# MCU_Extras.net
KiCad netlist of a schematic drawn in Altium Designer
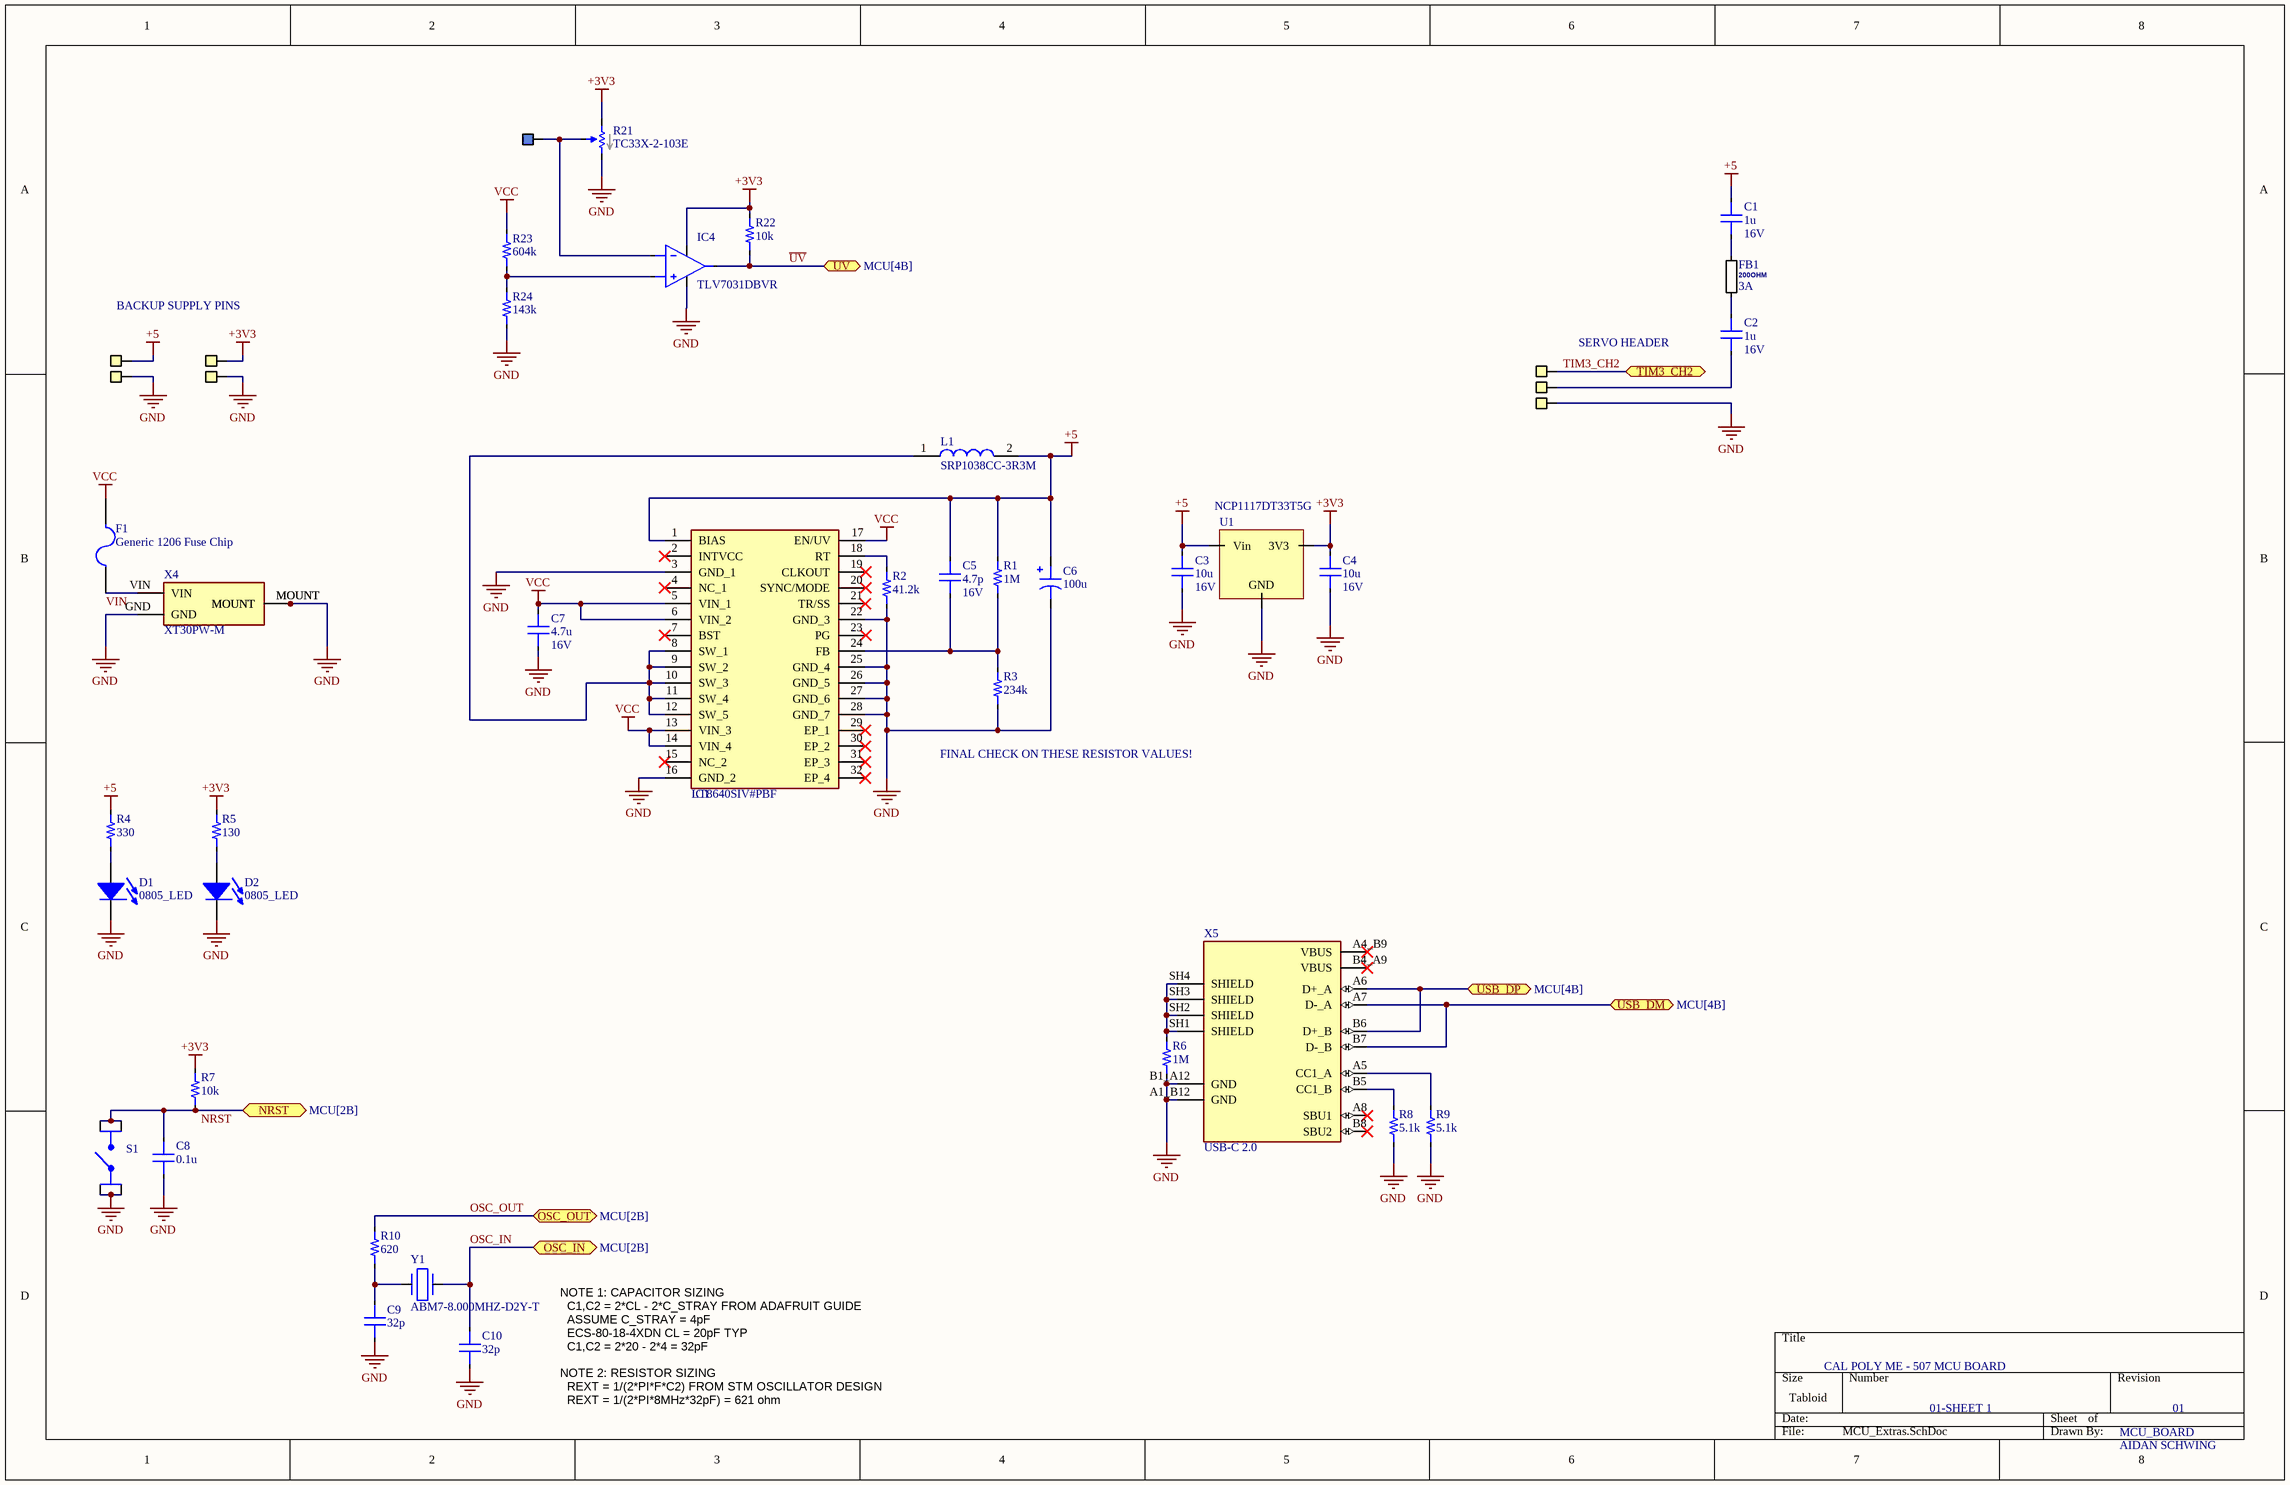
[diagram p0: MCU_Extras.SchDoc]

(export (version "E")
  (design (tool "Eeschema 10.0.6"))
  (components
    (comp (ref "C1")
      (value "1u")
      (footprint "0603_CAP")
      (fields (field (name "VOLTAGE") "16V") (field (name "Comment") "Capacitor"))
      (libsource (lib "Capacitors") (part "Capacitor"))
    )
    (comp (ref "C2")
      (value "1u")
      (footprint "0603_CAP")
      (fields (field (name "VOLTAGE") "16V") (field (name "Comment") "Capacitor"))
      (libsource (lib "Capacitors") (part "Capacitor"))
    )
    (comp (ref "C3")
      (value "10u")
      (footprint "0805_CAP")
      (fields (field (name "VOLTAGE") "16V") (field (name "Comment") "Capacitor"))
      (libsource (lib "Capacitors") (part "Capacitor"))
    )
    (comp (ref "C4")
      (value "10u")
      (footprint "0805_CAP")
      (fields (field (name "VOLTAGE") "16V") (field (name "Comment") "Capacitor"))
      (libsource (lib "Capacitors") (part "Capacitor"))
    )
    (comp (ref "C5")
      (value "4.7p")
      (footprint "0603_CAP")
      (fields (field (name "VOLTAGE") "16V") (field (name "Comment") "Capacitor"))
      (libsource (lib "Capacitors") (part "Capacitor"))
    )
    (comp (ref "C6")
      (value "100u")
      (footprint "6.60x6.60x8.00mm_E_CAP")
      (description "CAP ALUM 100UF 20% 16V SMD")
      (fields (field (name "Comment") "865080343009"))
      (libsource (lib "Capacitors") (part "865080343009"))
    )
    (comp (ref "C7")
      (value "4.7u")
      (footprint "0805_CAP")
      (fields (field (name "VOLTAGE") "16V") (field (name "Comment") "Capacitor"))
      (libsource (lib "Capacitors") (part "Capacitor"))
    )
    (comp (ref "C8")
      (value "0.1u")
      (footprint "0805_CAP")
      (fields (field (name "Comment") "Capacitor"))
      (libsource (lib "Capacitors") (part "Capacitor"))
    )
    (comp (ref "C9")
      (value "32p")
      (footprint "0805_CAP")
      (fields (field (name "Comment") "Capacitor"))
      (libsource (lib "Capacitors") (part "Capacitor"))
    )
    (comp (ref "C10")
      (value "32p")
      (footprint "0805_CAP")
      (fields (field (name "Comment") "Capacitor"))
      (libsource (lib "Capacitors") (part "Capacitor"))
    )
    (comp (ref "D1")
      (value "0805_LED")
      (footprint "0805_LED")
      (description "Generic 0805 LED")
      (libsource (lib "Diodes") (part "0805_LED"))
    )
    (comp (ref "D2")
      (value "0805_LED")
      (footprint "0805_LED")
      (description "Generic 0805 LED")
      (libsource (lib "Diodes") (part "0805_LED"))
    )
    (comp (ref "F1")
      (value "Generic 1206 Fuse Chip")
      (footprint "1206_RES")
      (libsource (lib "Fuses") (part "Generic 1206 Fuse Chip"))
    )
    (comp (ref "FB1")
      (value "*")
      (footprint "0805_Ferrite")
      (fields (field (name "=Z@100MHZ") "200OHM") (field (name "IMAX") "3A"))
      (libsource (lib "Magnetic") (part "ChipFerrite"))
    )
    (comp (ref "IC1")
      (value "LT8640SIV#PBF")
      (footprint "507_Part_Footprints:LT8640SIVPBF")
      (description "Integrated Circuit")
      (fields (field (name "MOUSER PART NUMBER") "584-LT8640SIVPBF"))
      (libsource (lib "507_Parts") (part "LT8640SIV#PBF"))
    )
    (comp (ref "IC4")
      (value "TLV7031DBVR")
      (footprint "507_Part_Footprints:SOT95P280X145-5N")
      (fields (field (name "MOUSER PART NUMBER") "595-TLV7031DBVR"))
      (libsource (lib "507_Parts") (part "TLV7031DBVR"))
    )
    (comp (ref "L1")
      (value "SRP1038CC-3R3M")
      (footprint "INDPM110100X400N")
      (description "Inductor, 3.3uH")
      (fields (field (name "MANUFACTURER_PART_NUMBER") "SRP1038CC-4R7M"))
      (libsource (lib "507_Parts") (part "SRP1038CC-3R3M"))
    )
    (comp (ref "R1")
      (value "1M")
      (footprint "0805_RES")
      (fields (field (name "Comment") "Resistor"))
      (libsource (lib "Resistors") (part "Resistor"))
    )
    (comp (ref "R2")
      (value "41.2k")
      (footprint "0805_RES")
      (fields (field (name "Comment") "Resistor"))
      (libsource (lib "Resistors") (part "Resistor"))
    )
    (comp (ref "R3")
      (value "234k")
      (footprint "0805_RES")
      (fields (field (name "Comment") "Resistor"))
      (libsource (lib "Resistors") (part "Resistor"))
    )
    (comp (ref "R4")
      (value "330")
      (footprint "0603_RES")
      (fields (field (name "Comment") "Resistor"))
      (libsource (lib "Resistors") (part "Resistor"))
    )
    (comp (ref "R5")
      (value "130")
      (footprint "0603_RES")
      (fields (field (name "Comment") "Resistor"))
      (libsource (lib "Resistors") (part "Resistor"))
    )
    (comp (ref "R6")
      (value "1M")
      (footprint "0805_RES")
      (fields (field (name "Comment") "Resistor"))
      (libsource (lib "Resistors") (part "Resistor"))
    )
    (comp (ref "R7")
      (value "10k")
      (footprint "0603_RES")
      (fields (field (name "Comment") "Resistor"))
      (libsource (lib "Resistors") (part "Resistor"))
    )
    (comp (ref "R8")
      (value "5.1k")
      (footprint "0805_RES")
      (fields (field (name "Comment") "Resistor"))
      (libsource (lib "Resistors") (part "Resistor"))
    )
    (comp (ref "R9")
      (value "5.1k")
      (footprint "0805_RES")
      (fields (field (name "Comment") "Resistor"))
      (libsource (lib "Resistors") (part "Resistor"))
    )
    (comp (ref "R10")
      (value "620")
      (footprint "0805_RES")
      (fields (field (name "Comment") "Resistor"))
      (libsource (lib "Resistors") (part "Resistor"))
    )
    (comp (ref "R21")
      (value "TC33X-2-103E")
      (footprint "35WR")
      (description "0.1W, 1/10W J Lead Surface Mount Trimmer Potentiometer Cermet Turn Top Adjustment")
      (fields (field (name "POWER") "1/10W"))
      (libsource (lib "Resistors") (part "TC33X-2-103E"))
    )
    (comp (ref "R22")
      (value "10k")
      (footprint "0805_RES")
      (fields (field (name "Comment") "Resistor"))
      (libsource (lib "Resistors") (part "Resistor"))
    )
    (comp (ref "R23")
      (value "604k")
      (footprint "0805_RES")
      (fields (field (name "Comment") "Resistor"))
      (libsource (lib "Resistors") (part "Resistor"))
    )
    (comp (ref "R24")
      (value "143k")
      (footprint "0805_RES")
      (fields (field (name "Comment") "Resistor"))
      (libsource (lib "Resistors") (part "Resistor"))
    )
    (comp (ref "S1")
      (value "TactileSwitch")
      (footprint "6mmTactileSwitch_ThroughHole")
      (description "Generic 6mm Through Hole Tactile Switch")
      (libsource (lib "ElectroMechanical") (part "TactileSwitch"))
    )
    (comp (ref "U1")
      (value "NCP1117DT33T5G")
      (footprint "DPAK3_TO-252-3")
      (description "IC REG LINEAR 3.3V 1A DPAK")
      (libsource (lib "Power") (part "NCP1117DT33T5G"))
    )
    (comp (ref "X1")
      (value "GenericPinHeader(0.1in)")
      (footprint "GenericPinHeader(.1in)")
      (description "Generic .1in(2.54mm) pitch pin header")
      (libsource (lib "Connectors") (part "GenericPinHeader(0.1in)"))
    )
    (comp (ref "X2")
      (value "GenericPinHeader(0.1in)")
      (footprint "GenericPinHeader(.1in)")
      (description "Generic .1in(2.54mm) pitch pin header")
      (libsource (lib "Connectors") (part "GenericPinHeader(0.1in)"))
    )
    (comp (ref "X3")
      (value "GenericPinHeader(0.1in)")
      (footprint "GenericPinHeader(.1in)")
      (description "Generic .1in(2.54mm) pitch pin header")
      (libsource (lib "Connectors") (part "GenericPinHeader(0.1in)"))
    )
    (comp (ref "X4")
      (value "XT30PW-M")
      (footprint "XT30PWM")
      (description "Socket; DC supply; XT30; male; PIN: 2; on PCBs; THT; yellow; 15A; 500V")
      (libsource (lib "Connectors") (part "XT30PW-M"))
    )
    (comp (ref "X5")
      (value "USB-C 2.0")
      (footprint "AMPHENOL_12402012E212A")
      (description "CONN RCP USB2.0 TYP C 24P SMD RA")
      (fields (field (name "MF") "{'manufacturer': u'Amphenol'}") (field (name "MP") "12402012E212A"))
      (libsource (lib "507_Parts") (part "12402012E212A"))
    )
    (comp (ref "X11")
      (value "HeaderPad")
      (footprint "HeaderPad")
      (description "Pad for pin header")
      (libsource (lib "Connectors") (part "HeaderPad"))
    )
    (comp (ref "X19")
      (value "GenericPinHeader(0.1in)")
      (footprint "GenericPinHeader(.1in)")
      (description "Generic .1in(2.54mm) pitch pin header")
      (libsource (lib "Connectors") (part "GenericPinHeader(0.1in)"))
    )
    (comp (ref "X22")
      (value "GenericPinHeader(0.1in)")
      (footprint "GenericPinHeader(.1in)")
      (description "Generic .1in(2.54mm) pitch pin header")
      (libsource (lib "Connectors") (part "GenericPinHeader(0.1in)"))
    )
    (comp (ref "X23")
      (value "GenericPinHeader(0.1in)")
      (footprint "GenericPinHeader(.1in)")
      (description "Generic .1in(2.54mm) pitch pin header")
      (libsource (lib "Connectors") (part "GenericPinHeader(0.1in)"))
    )
    (comp (ref "X26")
      (value "GenericPinHeader(0.1in)")
      (footprint "GenericPinHeader(.1in)")
      (description "Generic .1in(2.54mm) pitch pin header")
      (libsource (lib "Connectors") (part "GenericPinHeader(0.1in)"))
    )
    (comp (ref "Y1")
      (value "ABM7-8.000MHZ-D2Y-T")
      (footprint "ABM7")
      (description "Crystal or Oscillator")
      (fields (field (name "MOUSER PART NUMBER") "815-ABM7-8-D2Y-T"))
      (libsource (lib "507_Parts") (part "ABM7-8.000MHZ-D2Y-T"))
    )
  )
  (nets
    (net (code "1") (name "+3V3") (class "Default")
      (node (ref "C4") (pin "1") (pinfunction "1_1") (pintype "passive"))
      (node (ref "IC4") (pin "5") (pinfunction "VCC_5") (pintype "passive"))
      (node (ref "R21") (pin "1") (pinfunction "1_1") (pintype "passive"))
      (node (ref "R22") (pin "2") (pinfunction "2_2") (pintype "passive"))
      (node (ref "R5") (pin "2") (pinfunction "2_2") (pintype "passive"))
      (node (ref "R7") (pin "2") (pinfunction "2_2") (pintype "passive"))
      (node (ref "U1") (pin "4") (pinfunction "3V3_4") (pintype "passive"))
      (node (ref "X22") (pin "1") (pinfunction "Pin_1") (pintype "passive"))
    )
    (net (code "2") (name "+5") (class "Default")
      (node (ref "C1") (pin "1") (pinfunction "1_1") (pintype "passive"))
      (node (ref "C3") (pin "1") (pinfunction "1_1") (pintype "passive"))
      (node (ref "C5") (pin "1") (pinfunction "1_1") (pintype "passive"))
      (node (ref "C6") (pin "1") (pinfunction "1_1") (pintype "passive"))
      (node (ref "IC1") (pin "1") (pinfunction "BIAS_1") (pintype "passive"))
      (node (ref "L1") (pin "2") (pinfunction "2_2") (pintype "passive"))
      (node (ref "R1") (pin "2") (pinfunction "2_2") (pintype "passive"))
      (node (ref "R4") (pin "2") (pinfunction "2_2") (pintype "passive"))
      (node (ref "U1") (pin "3") (pinfunction "Vin_3") (pintype "passive"))
      (node (ref "X19") (pin "1") (pinfunction "Pin_1") (pintype "passive"))
    )
    (net (code "3") (name "/NRST") (class "Default")
      (node (ref "C8") (pin "2") (pinfunction "2_2") (pintype "passive"))
      (node (ref "R7") (pin "1") (pinfunction "1_1") (pintype "passive"))
      (node (ref "S1") (pin "3") (pinfunction "3_3") (pintype "passive"))
      (node (ref "S1") (pin "4") (pinfunction "4_4") (pintype "passive"))
    )
    (net (code "4") (name "/OSC_IN") (class "Default")
      (node (ref "C10") (pin "2") (pinfunction "2_2") (pintype "passive"))
      (node (ref "Y1") (pin "2") (pinfunction "2_2") (pintype "passive"))
    )
    (net (code "5") (name "/OSC_OUT") (class "Default")
      (node (ref "R10") (pin "2") (pinfunction "2_2") (pintype "passive"))
    )
    (net (code "6") (name "/TIM3_CH2") (class "Default")
      (node (ref "X1") (pin "1") (pinfunction "Pin_1") (pintype "passive"))
    )
    (net (code "7") (name "/USB_DM") (class "Default")
      (node (ref "X5") (pin "A7") (pinfunction "D-_A_A7") (pintype "bidirectional"))
      (node (ref "X5") (pin "B7") (pinfunction "D-_B_B7") (pintype "bidirectional"))
    )
    (net (code "8") (name "/USB_DP") (class "Default")
      (node (ref "X5") (pin "A6") (pinfunction "D+_A_A6") (pintype "bidirectional"))
      (node (ref "X5") (pin "B6") (pinfunction "D+_B_B6") (pintype "bidirectional"))
    )
    (net (code "9") (name "/VIN") (class "Default")
      (node (ref "F1") (pin "1") (pinfunction "1_1") (pintype "passive"))
      (node (ref "X4") (pin "VIN") (pinfunction "VIN_VIN") (pintype "passive"))
    )
    (net (code "10") (name "/~{UV}") (class "Default")
      (node (ref "IC4") (pin "1") (pinfunction "OUT_1") (pintype "passive"))
      (node (ref "R22") (pin "1") (pinfunction "1_1") (pintype "passive"))
    )
    (net (code "11") (name "GND") (class "Default")
      (node (ref "C10") (pin "1") (pinfunction "1_1") (pintype "passive"))
      (node (ref "C3") (pin "2") (pinfunction "2_2") (pintype "passive"))
      (node (ref "C4") (pin "2") (pinfunction "2_2") (pintype "passive"))
      (node (ref "C6") (pin "2") (pinfunction "2_2") (pintype "passive"))
      (node (ref "C7") (pin "2") (pinfunction "2_2") (pintype "passive"))
      (node (ref "C8") (pin "1") (pinfunction "1_1") (pintype "passive"))
      (node (ref "C9") (pin "1") (pinfunction "1_1") (pintype "passive"))
      (node (ref "D1") (pin "2") (pinfunction "K_2") (pintype "passive"))
      (node (ref "D2") (pin "2") (pinfunction "K_2") (pintype "passive"))
      (node (ref "IC1") (pin "16") (pinfunction "GND_2_16") (pintype "passive"))
      (node (ref "IC1") (pin "22") (pinfunction "GND_3_22") (pintype "passive"))
      (node (ref "IC1") (pin "25") (pinfunction "GND_4_25") (pintype "passive"))
      (node (ref "IC1") (pin "26") (pinfunction "GND_5_26") (pintype "passive"))
      (node (ref "IC1") (pin "27") (pinfunction "GND_6_27") (pintype "passive"))
      (node (ref "IC1") (pin "28") (pinfunction "GND_7_28") (pintype "passive"))
      (node (ref "IC1") (pin "3") (pinfunction "GND_1_3") (pintype "passive"))
      (node (ref "IC4") (pin "2") (pinfunction "VEE_2") (pintype "passive"))
      (node (ref "R2") (pin "1") (pinfunction "1_1") (pintype "passive"))
      (node (ref "R21") (pin "3") (pinfunction "3_3") (pintype "passive"))
      (node (ref "R24") (pin "1") (pinfunction "1_1") (pintype "passive"))
      (node (ref "R3") (pin "1") (pinfunction "1_1") (pintype "passive"))
      (node (ref "R6") (pin "1") (pinfunction "1_1") (pintype "passive"))
      (node (ref "R8") (pin "1") (pinfunction "1_1") (pintype "passive"))
      (node (ref "R9") (pin "1") (pinfunction "1_1") (pintype "passive"))
      (node (ref "S1") (pin "1") (pinfunction "1_1") (pintype "passive"))
      (node (ref "S1") (pin "2") (pinfunction "2_2") (pintype "passive"))
      (node (ref "U1") (pin "1") (pinfunction "GND_1") (pintype "passive"))
      (node (ref "X23") (pin "1") (pinfunction "Pin_1") (pintype "passive"))
      (node (ref "X26") (pin "1") (pinfunction "Pin_1") (pintype "passive"))
      (node (ref "X3") (pin "1") (pinfunction "Pin_1") (pintype "passive"))
      (node (ref "X4") (pin "GND") (pinfunction "GND_GND") (pintype "passive"))
      (node (ref "X4") (pin "MOUNT") (pinfunction "MOUNT_MOUNT") (pintype "passive"))
      (node (ref "X5") (pin "A1_B12") (pinfunction "GND_A1_B12") (pintype "power_in"))
      (node (ref "X5") (pin "B1_A12") (pinfunction "GND_B1_A12") (pintype "power_in"))
    )
    (net (code "12") (name "Net-(C1-Pad2)") (class "Default")
      (node (ref "C1") (pin "2") (pinfunction "2_2") (pintype "passive"))
      (node (ref "FB1") (pin "2") (pinfunction "2_2") (pintype "passive"))
    )
    (net (code "13") (name "Net-(C2-Pad1)") (class "Default")
      (node (ref "C2") (pin "1") (pinfunction "1_1") (pintype "passive"))
      (node (ref "FB1") (pin "1") (pinfunction "1_1") (pintype "passive"))
    )
    (net (code "14") (name "Net-(C9-Pad2)") (class "Default")
      (node (ref "C9") (pin "2") (pinfunction "2_2") (pintype "passive"))
      (node (ref "R10") (pin "1") (pinfunction "1_1") (pintype "passive"))
      (node (ref "Y1") (pin "1") (pinfunction "1_1") (pintype "passive"))
    )
    (net (code "15") (name "Net-(D1-A)") (class "Default")
      (node (ref "D1") (pin "1") (pinfunction "A_1") (pintype "passive"))
      (node (ref "R4") (pin "1") (pinfunction "1_1") (pintype "passive"))
    )
    (net (code "16") (name "Net-(D2-A)") (class "Default")
      (node (ref "D2") (pin "1") (pinfunction "A_1") (pintype "passive"))
      (node (ref "R5") (pin "1") (pinfunction "1_1") (pintype "passive"))
    )
    (net (code "17") (name "Net-(IC1-FB)") (class "Default")
      (node (ref "C5") (pin "2") (pinfunction "2_2") (pintype "passive"))
      (node (ref "IC1") (pin "24") (pinfunction "FB_24") (pintype "passive"))
      (node (ref "R1") (pin "1") (pinfunction "1_1") (pintype "passive"))
      (node (ref "R3") (pin "2") (pinfunction "2_2") (pintype "passive"))
    )
    (net (code "18") (name "Net-(IC1-RT)") (class "Default")
      (node (ref "IC1") (pin "18") (pinfunction "RT_18") (pintype "passive"))
      (node (ref "R2") (pin "2") (pinfunction "2_2") (pintype "passive"))
    )
    (net (code "19") (name "Net-(IC1-SW_1)") (class "Default")
      (node (ref "IC1") (pin "10") (pinfunction "SW_3_10") (pintype "passive"))
      (node (ref "IC1") (pin "11") (pinfunction "SW_4_11") (pintype "passive"))
      (node (ref "IC1") (pin "12") (pinfunction "SW_5_12") (pintype "passive"))
      (node (ref "IC1") (pin "8") (pinfunction "SW_1_8") (pintype "passive"))
      (node (ref "IC1") (pin "9") (pinfunction "SW_2_9") (pintype "passive"))
      (node (ref "L1") (pin "1") (pinfunction "1_1") (pintype "passive"))
    )
    (net (code "20") (name "Net-(IC4-IN+)") (class "Default")
      (node (ref "IC4") (pin "3") (pinfunction "IN+_3") (pintype "passive"))
      (node (ref "R23") (pin "1") (pinfunction "1_1") (pintype "passive"))
      (node (ref "R24") (pin "2") (pinfunction "2_2") (pintype "passive"))
    )
    (net (code "21") (name "Net-(IC4-IN-)") (class "Default")
      (node (ref "IC4") (pin "4") (pinfunction "IN-_4") (pintype "passive"))
      (node (ref "R21") (pin "2") (pinfunction "2_2") (pintype "passive"))
      (node (ref "X11") (pin "1") (pinfunction "Pin_1") (pintype "passive"))
    )
    (net (code "22") (name "Net-(R6-Pad2)") (class "Default")
      (node (ref "R6") (pin "2") (pinfunction "2_2") (pintype "passive"))
      (node (ref "X5") (pin "SH1") (pinfunction "SHIELD_SH1") (pintype "passive"))
      (node (ref "X5") (pin "SH2") (pinfunction "SHIELD_SH2") (pintype "passive"))
      (node (ref "X5") (pin "SH3") (pinfunction "SHIELD_SH3") (pintype "passive"))
      (node (ref "X5") (pin "SH4") (pinfunction "SHIELD_SH4") (pintype "passive"))
    )
    (net (code "23") (name "Net-(X2-Pin)") (class "Default")
      (node (ref "C2") (pin "2") (pinfunction "2_2") (pintype "passive"))
      (node (ref "X2") (pin "1") (pinfunction "Pin_1") (pintype "passive"))
    )
    (net (code "24") (name "Net-(X5-CC1_A)") (class "Default")
      (node (ref "R9") (pin "2") (pinfunction "2_2") (pintype "passive"))
      (node (ref "X5") (pin "A5") (pinfunction "CC1_A_A5") (pintype "bidirectional"))
    )
    (net (code "25") (name "Net-(X5-CC1_B)") (class "Default")
      (node (ref "R8") (pin "2") (pinfunction "2_2") (pintype "passive"))
      (node (ref "X5") (pin "B5") (pinfunction "CC1_B_B5") (pintype "bidirectional"))
    )
    (net (code "26") (name "VCC") (class "Default")
      (node (ref "C7") (pin "1") (pinfunction "1_1") (pintype "passive"))
      (node (ref "F1") (pin "2") (pinfunction "2_2") (pintype "passive"))
      (node (ref "IC1") (pin "13") (pinfunction "VIN_3_13") (pintype "passive"))
      (node (ref "IC1") (pin "14") (pinfunction "VIN_4_14") (pintype "passive"))
      (node (ref "IC1") (pin "17") (pinfunction "EN/UV_17") (pintype "passive"))
      (node (ref "IC1") (pin "5") (pinfunction "VIN_1_5") (pintype "passive"))
      (node (ref "IC1") (pin "6") (pinfunction "VIN_2_6") (pintype "passive"))
      (node (ref "R23") (pin "2") (pinfunction "2_2") (pintype "passive"))
    )
    (net (code "27") (name "unconnected-(IC1-BST-Pad7)") (class "Default")
      (node (ref "IC1") (pin "7") (pinfunction "BST_7") (pintype "passive+no_connect"))
    )
    (net (code "28") (name "unconnected-(IC1-CLKOUT-Pad19)") (class "Default")
      (node (ref "IC1") (pin "19") (pinfunction "CLKOUT_19") (pintype "passive"))
    )
    (net (code "29") (name "unconnected-(IC1-EP_1-Pad29)") (class "Default")
      (node (ref "IC1") (pin "29") (pinfunction "EP_1_29") (pintype "passive+no_connect"))
    )
    (net (code "30") (name "unconnected-(IC1-EP_2-Pad30)") (class "Default")
      (node (ref "IC1") (pin "30") (pinfunction "EP_2_30") (pintype "passive+no_connect"))
    )
    (net (code "31") (name "unconnected-(IC1-EP_3-Pad31)") (class "Default")
      (node (ref "IC1") (pin "31") (pinfunction "EP_3_31") (pintype "passive+no_connect"))
    )
    (net (code "32") (name "unconnected-(IC1-EP_4-Pad32)") (class "Default")
      (node (ref "IC1") (pin "32") (pinfunction "EP_4_32") (pintype "passive+no_connect"))
    )
    (net (code "33") (name "unconnected-(IC1-INTVCC-Pad2)") (class "Default")
      (node (ref "IC1") (pin "2") (pinfunction "INTVCC_2") (pintype "passive+no_connect"))
    )
    (net (code "34") (name "unconnected-(IC1-NC_1-Pad4)") (class "Default")
      (node (ref "IC1") (pin "4") (pinfunction "NC_1_4") (pintype "passive+no_connect"))
    )
    (net (code "35") (name "unconnected-(IC1-NC_2-Pad15)") (class "Default")
      (node (ref "IC1") (pin "15") (pinfunction "NC_2_15") (pintype "passive+no_connect"))
    )
    (net (code "36") (name "unconnected-(IC1-PG-Pad23)") (class "Default")
      (node (ref "IC1") (pin "23") (pinfunction "PG_23") (pintype "passive"))
    )
    (net (code "37") (name "unconnected-(IC1-SYNC{slash}MODE-Pad20)") (class "Default")
      (node (ref "IC1") (pin "20") (pinfunction "SYNC/MODE_20") (pintype "passive"))
    )
    (net (code "38") (name "unconnected-(IC1-TR{slash}SS-Pad21)") (class "Default")
      (node (ref "IC1") (pin "21") (pinfunction "TR/SS_21") (pintype "passive+no_connect"))
    )
    (net (code "39") (name "unconnected-(X5-SBU1-PadA8)") (class "Default")
      (node (ref "X5") (pin "A8") (pinfunction "SBU1_A8") (pintype "bidirectional+no_connect"))
    )
    (net (code "40") (name "unconnected-(X5-SBU2-PadB8)") (class "Default")
      (node (ref "X5") (pin "B8") (pinfunction "SBU2_B8") (pintype "bidirectional+no_connect"))
    )
    (net (code "41") (name "unconnected-(X5-VBUS-PadA4_B9)") (class "Default")
      (node (ref "X5") (pin "A4_B9") (pinfunction "VBUS_A4_B9") (pintype "power_in+no_connect"))
    )
    (net (code "42") (name "unconnected-(X5-VBUS-PadB4_A9)") (class "Default")
      (node (ref "X5") (pin "B4_A9") (pinfunction "VBUS_B4_A9") (pintype "power_in+no_connect"))
    )
  )
)
